# cociclo_03_01.net
KiCad netlist of a schematic drawn in EAGLE
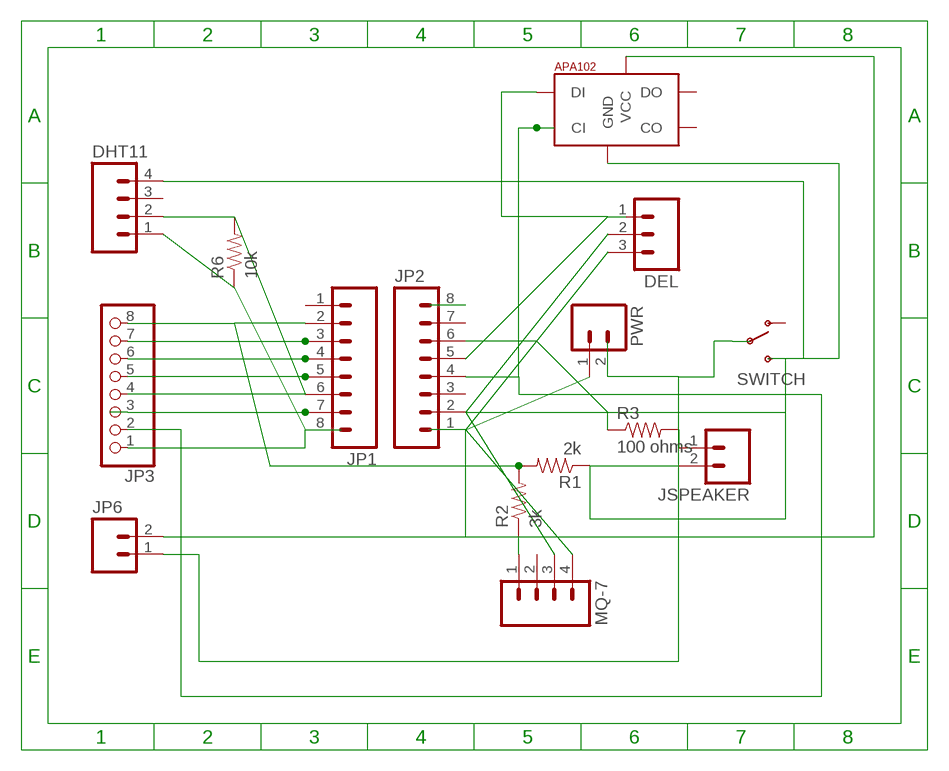
[diagram p0: schematic, sheet 1]

(export (version "E")
  (design (tool "Eeschema 10.0.6"))
  (components
    (comp (ref "DEL")
      (value "M03PTH")
      (footprint "eagle-import:1X03")
      (libsource (lib "eagle-import") (part "M03PTH"))
    )
    (comp (ref "DHT11")
      (value "M04PTH")
      (footprint "eagle-import:1X04")
      (libsource (lib "eagle-import") (part "M04PTH"))
    )
    (comp (ref "JP1")
      (value "M08")
      (footprint "eagle-import:1X08_ROUND")
      (libsource (lib "eagle-import") (part "M08"))
    )
    (comp (ref "JP2")
      (value "M08")
      (footprint "eagle-import:1X08_ROUND")
      (libsource (lib "eagle-import") (part "M08"))
    )
    (comp (ref "JP3")
      (value "PINHD-1X8-3.5MM")
      (footprint "eagle-import:1X08-3.5MM")
      (libsource (lib "eagle-import") (part "PINHD-1X8-3.5MM"))
    )
    (comp (ref "JP6")
      (value "M023.5MM")
      (footprint "eagle-import:SCREWTERMINAL-3.5MM-2")
      (libsource (lib "eagle-import") (part "M023.5MM"))
    )
    (comp (ref "JSPEAKER")
      (value "M02PTH")
      (footprint "eagle-import:1X02")
      (libsource (lib "eagle-import") (part "M02PTH"))
    )
    (comp (ref "LED")
      (value "APA1025050")
      (footprint "eagle-import:APA102_5050")
      (libsource (lib "eagle-import") (part "APA1025050"))
    )
    (comp (ref "MQ-7")
      (value "M04PTH")
      (footprint "eagle-import:1X04")
      (libsource (lib "eagle-import") (part "M04PTH"))
    )
    (comp (ref "PWR")
      (value "M02LOCK_LONGPADS")
      (footprint "eagle-import:1X02_LOCK_LONGPADS")
      (libsource (lib "eagle-import") (part "M02LOCK_LONGPADS"))
    )
    (comp (ref "R1")
      (value "2k")
      (footprint "eagle-import:1206")
      (libsource (lib "eagle-import") (part "RESISTOR1206"))
    )
    (comp (ref "R2")
      (value "3k")
      (footprint "eagle-import:1206")
      (libsource (lib "eagle-import") (part "RESISTOR1206"))
    )
    (comp (ref "R3")
      (value "100 ohms")
      (footprint "eagle-import:1206")
      (libsource (lib "eagle-import") (part "RESISTOR1206"))
    )
    (comp (ref "R6")
      (value "10k")
      (footprint "eagle-import:1206")
      (libsource (lib "eagle-import") (part "RESISTOR1206"))
    )
    (comp (ref "SWITCH")
      (value "SWITCH-SPDTKIT")
      (footprint "eagle-import:SWITCH-SPDT_KIT")
      (libsource (lib "eagle-import") (part "SWITCH-SPDTKIT"))
    )
  )
  (nets
    (net (code "1") (name "Net-(DHT11-Pad1)") (class "Default")
      (node (ref "DHT11") (pin "1") (pinfunction "1_1") (pintype "passive"))
      (node (ref "JP1") (pin "8") (pinfunction "8_8") (pintype "passive"))
      (node (ref "JP3") (pin "1") (pinfunction "1_1") (pintype "passive"))
      (node (ref "R6") (pin "1") (pinfunction "1_1") (pintype "passive"))
    )
    (net (code "2") (name "Net-(DHT11-Pad2)") (class "Default")
      (node (ref "DHT11") (pin "2") (pinfunction "2_2") (pintype "passive"))
      (node (ref "JP1") (pin "6") (pinfunction "6_6") (pintype "passive"))
      (node (ref "JP3") (pin "4") (pinfunction "4_4") (pintype "passive"))
      (node (ref "R6") (pin "2") (pinfunction "2_2") (pintype "passive"))
    )
    (net (code "3") (name "Net-(JP1-Pad2)") (class "Default")
      (node (ref "JP1") (pin "2") (pinfunction "2_2") (pintype "passive"))
      (node (ref "JP3") (pin "8") (pinfunction "8_8") (pintype "passive"))
      (node (ref "R1") (pin "2") (pinfunction "2_2") (pintype "passive"))
      (node (ref "R2") (pin "2") (pinfunction "2_2") (pintype "passive"))
    )
    (net (code "4") (name "Net-(JP1-Pad3)") (class "Default")
      (node (ref "JP1") (pin "3") (pinfunction "3_3") (pintype "passive"))
      (node (ref "JP3") (pin "7") (pinfunction "7_7") (pintype "passive"))
    )
    (net (code "5") (name "Net-(JP1-Pad4)") (class "Default")
      (node (ref "JP1") (pin "4") (pinfunction "4_4") (pintype "passive"))
      (node (ref "JP3") (pin "6") (pinfunction "6_6") (pintype "passive"))
    )
    (net (code "6") (name "Net-(JP1-Pad5)") (class "Default")
      (node (ref "JP1") (pin "5") (pinfunction "5_5") (pintype "passive"))
      (node (ref "JP3") (pin "5") (pinfunction "5_5") (pintype "passive"))
    )
    (net (code "7") (name "Net-(JP1-Pad7)") (class "Default")
      (node (ref "JP1") (pin "7") (pinfunction "7_7") (pintype "passive"))
      (node (ref "JP3") (pin "3") (pinfunction "3_3") (pintype "passive"))
    )
    (net (code "8") (name "Net-(JP2-Pad6)") (class "Default")
      (node (ref "JP2") (pin "6") (pinfunction "6_6") (pintype "passive"))
      (node (ref "R3") (pin "1") (pinfunction "1_1") (pintype "passive"))
    )
    (net (code "9") (name "Net-(JSPEAKER-Pad1)") (class "Default")
      (node (ref "JSPEAKER") (pin "1") (pinfunction "1_1") (pintype "passive"))
      (node (ref "R3") (pin "2") (pinfunction "2_2") (pintype "passive"))
    )
    (net (code "10") (name "Net-(LED-CI)") (class "Default")
      (node (ref "JP2") (pin "4") (pinfunction "4_4") (pintype "passive"))
      (node (ref "JP3") (pin "2") (pinfunction "2_2") (pintype "passive"))
      (node (ref "LED") (pin "5") (pinfunction "CI_5") (pintype "bidirectional"))
    )
    (net (code "11") (name "Net-(LED-DI)") (class "Default")
      (node (ref "DEL") (pin "1") (pinfunction "1_1") (pintype "passive"))
      (node (ref "JP2") (pin "5") (pinfunction "5_5") (pintype "passive"))
      (node (ref "LED") (pin "4") (pinfunction "DI_4") (pintype "bidirectional"))
    )
    (net (code "12") (name "Net-(LED-GND)") (class "Default")
      (node (ref "DEL") (pin "2") (pinfunction "2_2") (pintype "passive"))
      (node (ref "DHT11") (pin "4") (pinfunction "4_4") (pintype "passive"))
      (node (ref "JP2") (pin "2") (pinfunction "2_2") (pintype "passive"))
      (node (ref "JSPEAKER") (pin "2") (pinfunction "2_2") (pintype "passive"))
      (node (ref "LED") (pin "6") (pinfunction "GND_6") (pintype "bidirectional"))
      (node (ref "MQ-7") (pin "3") (pinfunction "3_3") (pintype "passive"))
      (node (ref "R1") (pin "1") (pinfunction "1_1") (pintype "passive"))
      (node (ref "SWITCH") (pin "3") (pinfunction "S_3") (pintype "passive"))
    )
    (net (code "13") (name "Net-(LED-VCC)") (class "Default")
      (node (ref "DEL") (pin "3") (pinfunction "3_3") (pintype "passive"))
      (node (ref "JP2") (pin "1") (pinfunction "1_1") (pintype "passive"))
      (node (ref "JP6") (pin "2") (pinfunction "2_2") (pintype "passive"))
      (node (ref "LED") (pin "1") (pinfunction "VCC_1") (pintype "bidirectional"))
      (node (ref "MQ-7") (pin "4") (pinfunction "4_4") (pintype "passive"))
      (node (ref "PWR") (pin "1") (pinfunction "1_1") (pintype "passive"))
    )
    (net (code "14") (name "Net-(MQ-7-Pad1)") (class "Default")
      (node (ref "MQ-7") (pin "1") (pinfunction "1_1") (pintype "passive"))
      (node (ref "R2") (pin "1") (pinfunction "1_1") (pintype "passive"))
    )
    (net (code "15") (name "Net-(SWITCH-P)") (class "Default")
      (node (ref "JP6") (pin "1") (pinfunction "1_1") (pintype "passive"))
      (node (ref "PWR") (pin "2") (pinfunction "2_2") (pintype "passive"))
      (node (ref "SWITCH") (pin "2") (pinfunction "P_2") (pintype "passive"))
    )
    (net (code "16") (name "unconnected-(DHT11-Pad3)") (class "Default")
      (node (ref "DHT11") (pin "3") (pinfunction "3_3") (pintype "passive"))
    )
    (net (code "17") (name "unconnected-(JP1-Pad1)") (class "Default")
      (node (ref "JP1") (pin "1") (pinfunction "1_1") (pintype "passive"))
    )
    (net (code "18") (name "unconnected-(JP2-Pad3)") (class "Default")
      (node (ref "JP2") (pin "3") (pinfunction "3_3") (pintype "passive"))
    )
    (net (code "19") (name "unconnected-(JP2-Pad7)") (class "Default")
      (node (ref "JP2") (pin "7") (pinfunction "7_7") (pintype "passive"))
    )
    (net (code "20") (name "unconnected-(JP2-Pad8)") (class "Default")
      (node (ref "JP2") (pin "8") (pinfunction "8_8") (pintype "passive"))
    )
    (net (code "21") (name "unconnected-(LED-CO-Pad2)") (class "Default")
      (node (ref "LED") (pin "2") (pinfunction "CO_2") (pintype "bidirectional"))
    )
    (net (code "22") (name "unconnected-(LED-DO-Pad3)") (class "Default")
      (node (ref "LED") (pin "3") (pinfunction "DO_3") (pintype "bidirectional"))
    )
    (net (code "23") (name "unconnected-(MQ-7-Pad2)") (class "Default")
      (node (ref "MQ-7") (pin "2") (pinfunction "2_2") (pintype "passive"))
    )
    (net (code "24") (name "unconnected-(SWITCH-O-Pad1)") (class "Default")
      (node (ref "SWITCH") (pin "1") (pinfunction "O_1") (pintype "passive"))
    )
  )
)
